# Guitar_Tuner.net
KiCad netlist of a schematic drawn in EAGLE
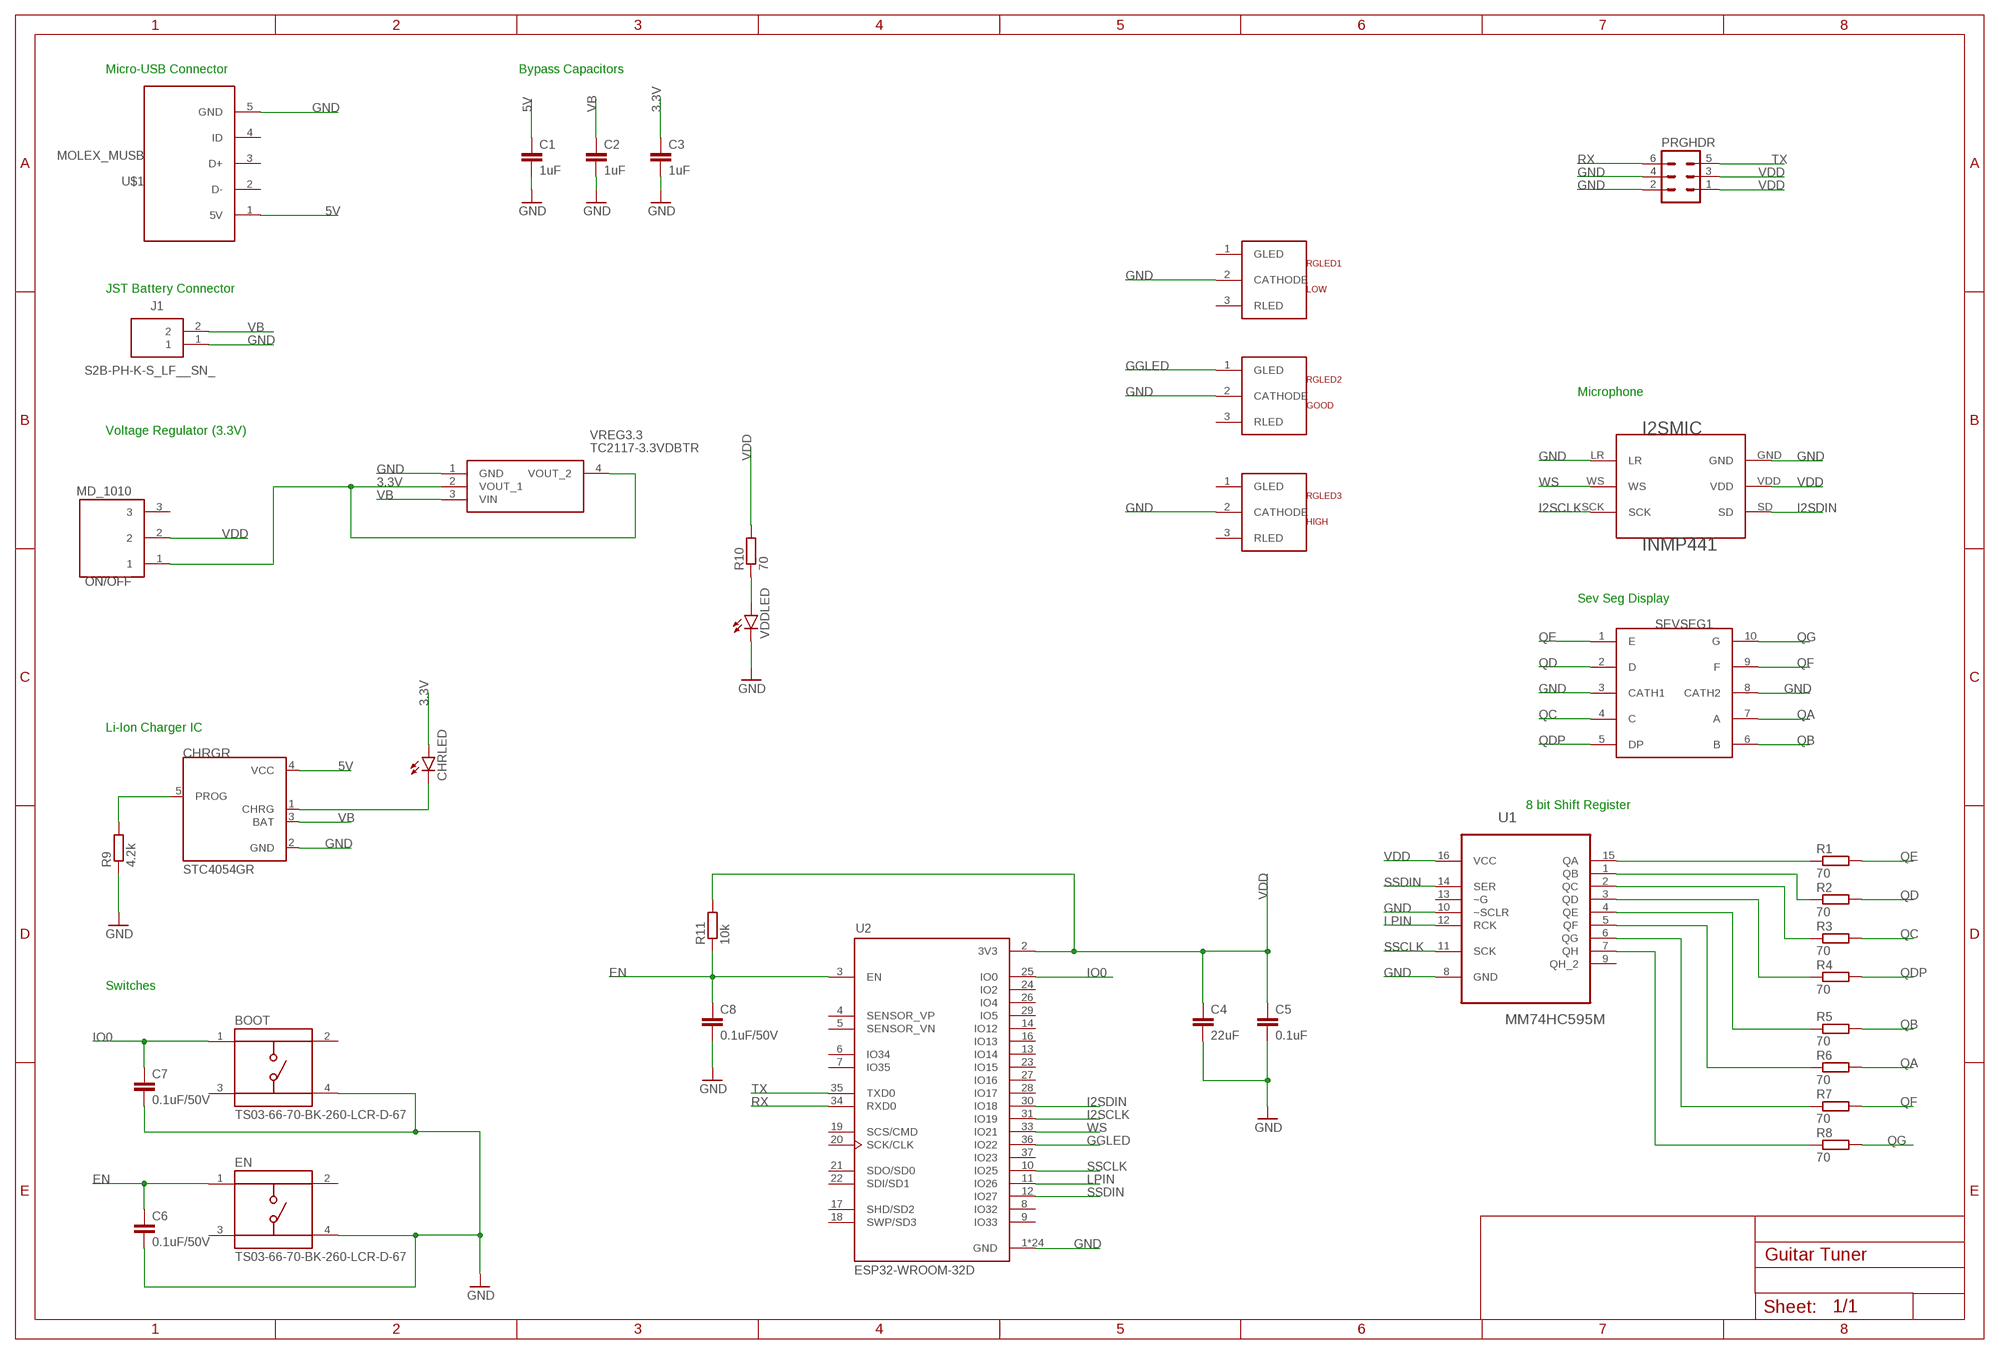
[diagram p0: schematic, sheet 1]

(export (version "E")
  (design (tool "Eeschema 10.0.6"))
  (components
    (comp (ref "BOOT")
      (value "TS03-66-70-BK-260-LCR-D-67")
      (footprint "eagle-import:SW_TS03-66-70-BK-260-LCR-D-67")
      (fields (field (name "MF") "CUI Devices"))
      (libsource (lib "eagle-import") (part "TS03-66-70-BK-260-LCR-D-67"))
    )
    (comp (ref "C1")
      (value "1uF")
      (footprint "eagle-import:C0805")
      (libsource (lib "eagle-import") (part "C-EUC0805"))
    )
    (comp (ref "C2")
      (value "1uF")
      (footprint "eagle-import:C0805")
      (libsource (lib "eagle-import") (part "C-EUC0805"))
    )
    (comp (ref "C3")
      (value "1uF")
      (footprint "eagle-import:C0805")
      (libsource (lib "eagle-import") (part "C-EUC0805"))
    )
    (comp (ref "C4")
      (value "22uF")
      (footprint "eagle-import:C0805")
      (libsource (lib "eagle-import") (part "C-EUC0805"))
    )
    (comp (ref "C5")
      (value "0.1uF")
      (footprint "eagle-import:C0805")
      (libsource (lib "eagle-import") (part "C-EUC0805"))
    )
    (comp (ref "C6")
      (value "0.1uF/50V")
      (footprint "eagle-import:C0805")
      (libsource (lib "eagle-import") (part "C-EUC0805"))
    )
    (comp (ref "C7")
      (value "0.1uF/50V")
      (footprint "eagle-import:C0805")
      (libsource (lib "eagle-import") (part "C-EUC0805"))
    )
    (comp (ref "C8")
      (value "0.1uF/50V")
      (footprint "eagle-import:C0805")
      (libsource (lib "eagle-import") (part "C-EUC0805"))
    )
    (comp (ref "CHRGR")
      (value "STC4054GR")
      (footprint "eagle-import:SOT95P280X110-5N")
      (fields (field (name "MF") "STMicroelectronics"))
      (libsource (lib "eagle-import") (part "STC4054GR"))
    )
    (comp (ref "CHRLED")
      (value "LED5MM")
      (footprint "eagle-import:LED5MM")
      (libsource (lib "eagle-import") (part "LED5MM"))
    )
    (comp (ref "EN")
      (value "TS03-66-70-BK-260-LCR-D-67")
      (footprint "eagle-import:SW_TS03-66-70-BK-260-LCR-D-67")
      (fields (field (name "MF") "CUI Devices"))
      (libsource (lib "eagle-import") (part "TS03-66-70-BK-260-LCR-D-67"))
    )
    (comp (ref "I2SMIC")
      (value "INMP441")
      (footprint "eagle-import:INMP441")
      (libsource (lib "eagle-import") (part "INMP441"))
    )
    (comp (ref "J1")
      (value "S2B-PH-K-S_LF__SN_")
      (footprint "eagle-import:SHDRRA2W50P0X200_1X2_590X760X4")
      (fields (field (name "ARROW_PART_NUMBER") "S2B-PH-K-S(LF)(SN)"))
      (libsource (lib "eagle-import") (part "S2B-PH-K-S_LF__SN_"))
    )
    (comp (ref "ON/OFF")
      (value "MD_1010")
      (footprint "eagle-import:MP_1010")
      (libsource (lib "eagle-import") (part "MD_1010"))
    )
    (comp (ref "PRGHDR")
      (value "MA03-2")
      (footprint "eagle-import:MA03-2")
      (libsource (lib "eagle-import") (part "MA03-2"))
    )
    (comp (ref "R1")
      (value "70")
      (footprint "eagle-import:R0805")
      (libsource (lib "eagle-import") (part "R-EU_R0805"))
    )
    (comp (ref "R2")
      (value "70")
      (footprint "eagle-import:R0805")
      (libsource (lib "eagle-import") (part "R-EU_R0805"))
    )
    (comp (ref "R3")
      (value "70")
      (footprint "eagle-import:R0805")
      (libsource (lib "eagle-import") (part "R-EU_R0805"))
    )
    (comp (ref "R4")
      (value "70")
      (footprint "eagle-import:R0805")
      (libsource (lib "eagle-import") (part "R-EU_R0805"))
    )
    (comp (ref "R5")
      (value "70")
      (footprint "eagle-import:R0805")
      (libsource (lib "eagle-import") (part "R-EU_R0805"))
    )
    (comp (ref "R6")
      (value "70")
      (footprint "eagle-import:R0805")
      (libsource (lib "eagle-import") (part "R-EU_R0805"))
    )
    (comp (ref "R7")
      (value "70")
      (footprint "eagle-import:R0805")
      (libsource (lib "eagle-import") (part "R-EU_R0805"))
    )
    (comp (ref "R8")
      (value "70")
      (footprint "eagle-import:R0805")
      (libsource (lib "eagle-import") (part "R-EU_R0805"))
    )
    (comp (ref "R9")
      (value "4.2k")
      (footprint "eagle-import:R0805")
      (libsource (lib "eagle-import") (part "R-EU_R0805"))
    )
    (comp (ref "R10")
      (value "70")
      (footprint "eagle-import:R0805")
      (libsource (lib "eagle-import") (part "R-EU_R0805"))
    )
    (comp (ref "R11")
      (value "10k")
      (footprint "eagle-import:0207_10")
      (libsource (lib "eagle-import") (part "R-EU_0207/10"))
    )
    (comp (ref "RGLED1")
      (value "LOW")
      (footprint "eagle-import:HLMP-0800")
      (libsource (lib "eagle-import") (part "HLMP-0800"))
    )
    (comp (ref "RGLED2")
      (value "GOOD")
      (footprint "eagle-import:HLMP-0800")
      (libsource (lib "eagle-import") (part "HLMP-0800"))
    )
    (comp (ref "RGLED3")
      (value "HIGH")
      (footprint "eagle-import:HLMP-0800")
      (libsource (lib "eagle-import") (part "HLMP-0800"))
    )
    (comp (ref "SEVSEG1")
      (value "LS0803GWK")
      (footprint "eagle-import:LS0803GWK")
      (libsource (lib "eagle-import") (part "LS0803GWK"))
    )
    (comp (ref "U$1")
      (value "MOLEX_MUSB")
      (footprint "eagle-import:MOLEX_MUSB")
      (libsource (lib "eagle-import") (part "MOLEX_MUSB"))
    )
    (comp (ref "U1")
      (value "MM74HC595M")
      (footprint "eagle-import:SOIC127P600X175-16N")
      (libsource (lib "eagle-import") (part "MM74HC595M"))
    )
    (comp (ref "U2")
      (value "ESP32-WROOM-32D")
      (footprint "eagle-import:MODULE_ESP32-WROOM-32D")
      (fields (field (name "MF") "Espressif Systems"))
      (libsource (lib "eagle-import") (part "ESP32-WROOM-32D"))
    )
    (comp (ref "VDDLED")
      (value "LED5MM")
      (footprint "eagle-import:LED5MM")
      (libsource (lib "eagle-import") (part "LED5MM"))
    )
    (comp (ref "VREG3.3")
      (value "TC2117-3.3VDBTR")
      (footprint "eagle-import:SOT230P700X180-4N")
      (fields (field (name "MOUSER_PART_NUMBER") "579-TC2117-3.3VDBTR"))
      (libsource (lib "eagle-import") (part "TC2117-3.3VDBTR"))
    )
  )
  (nets
    (net (code "1") (name "/3.3V") (class "Default")
      (node (ref "C3") (pin "1") (pinfunction "1_1") (pintype "passive"))
      (node (ref "CHRLED") (pin "A") (pinfunction "A_A") (pintype "passive"))
      (node (ref "ON/OFF") (pin "1") (pinfunction "1_1") (pintype "bidirectional"))
      (node (ref "VREG3.3") (pin "2") (pinfunction "VOUT_1_2") (pintype "power_in"))
      (node (ref "VREG3.3") (pin "4") (pinfunction "VOUT_2_4") (pintype "power_in"))
    )
    (net (code "2") (name "/5V") (class "Default")
      (node (ref "C1") (pin "1") (pinfunction "1_1") (pintype "passive"))
      (node (ref "CHRGR") (pin "4") (pinfunction "VCC_4") (pintype "power_in"))
      (node (ref "U$1") (pin "1") (pinfunction "5V_1") (pintype "bidirectional"))
    )
    (net (code "3") (name "/EN") (class "Default")
      (node (ref "C6") (pin "1") (pinfunction "1_1") (pintype "passive"))
      (node (ref "C8") (pin "1") (pinfunction "1_1") (pintype "passive"))
      (node (ref "EN") (pin "1") (pinfunction "1_1") (pintype "passive"))
      (node (ref "R11") (pin "1") (pinfunction "1_1") (pintype "passive"))
      (node (ref "U2") (pin "3") (pinfunction "EN_3") (pintype "input"))
    )
    (net (code "4") (name "/GGLED") (class "Default")
      (node (ref "RGLED2") (pin "1") (pinfunction "GLED_1") (pintype "bidirectional"))
      (node (ref "U2") (pin "36") (pinfunction "IO22_36") (pintype "bidirectional"))
    )
    (net (code "5") (name "/I2SCLK") (class "Default")
      (node (ref "I2SMIC") (pin "SCK") (pinfunction "SCK_SCK") (pintype "bidirectional"))
      (node (ref "U2") (pin "31") (pinfunction "IO19_31") (pintype "bidirectional"))
    )
    (net (code "6") (name "/I2SDIN") (class "Default")
      (node (ref "I2SMIC") (pin "SD") (pinfunction "SD_SD") (pintype "bidirectional"))
      (node (ref "U2") (pin "30") (pinfunction "IO18_30") (pintype "bidirectional"))
    )
    (net (code "7") (name "/IO0") (class "Default")
      (node (ref "BOOT") (pin "1") (pinfunction "1_1") (pintype "passive"))
      (node (ref "C7") (pin "1") (pinfunction "1_1") (pintype "passive"))
      (node (ref "U2") (pin "25") (pinfunction "IO0_25") (pintype "bidirectional"))
    )
    (net (code "8") (name "/LPIN") (class "Default")
      (node (ref "U1") (pin "12") (pinfunction "RCK_12") (pintype "input"))
      (node (ref "U2") (pin "11") (pinfunction "IO26_11") (pintype "bidirectional"))
    )
    (net (code "9") (name "/QA") (class "Default")
      (node (ref "R6") (pin "2") (pinfunction "2_2") (pintype "passive"))
      (node (ref "SEVSEG1") (pin "7") (pinfunction "A_7") (pintype "bidirectional"))
    )
    (net (code "10") (name "/QB") (class "Default")
      (node (ref "R5") (pin "2") (pinfunction "2_2") (pintype "passive"))
      (node (ref "SEVSEG1") (pin "6") (pinfunction "B_6") (pintype "bidirectional"))
    )
    (net (code "11") (name "/QC") (class "Default")
      (node (ref "R3") (pin "2") (pinfunction "2_2") (pintype "passive"))
      (node (ref "SEVSEG1") (pin "4") (pinfunction "C_4") (pintype "bidirectional"))
    )
    (net (code "12") (name "/QD") (class "Default")
      (node (ref "R2") (pin "2") (pinfunction "2_2") (pintype "passive"))
      (node (ref "SEVSEG1") (pin "2") (pinfunction "D_2") (pintype "bidirectional"))
    )
    (net (code "13") (name "/QDP") (class "Default")
      (node (ref "R4") (pin "2") (pinfunction "2_2") (pintype "passive"))
      (node (ref "SEVSEG1") (pin "5") (pinfunction "DP_5") (pintype "bidirectional"))
    )
    (net (code "14") (name "/QE") (class "Default")
      (node (ref "R1") (pin "2") (pinfunction "2_2") (pintype "passive"))
      (node (ref "SEVSEG1") (pin "1") (pinfunction "E_1") (pintype "bidirectional"))
    )
    (net (code "15") (name "/QF") (class "Default")
      (node (ref "R7") (pin "2") (pinfunction "2_2") (pintype "passive"))
      (node (ref "SEVSEG1") (pin "9") (pinfunction "F_9") (pintype "bidirectional"))
    )
    (net (code "16") (name "/QG") (class "Default")
      (node (ref "R8") (pin "2") (pinfunction "2_2") (pintype "passive"))
      (node (ref "SEVSEG1") (pin "10") (pinfunction "G_10") (pintype "bidirectional"))
    )
    (net (code "17") (name "/RX") (class "Default")
      (node (ref "PRGHDR") (pin "6") (pinfunction "6_6") (pintype "passive"))
      (node (ref "U2") (pin "34") (pinfunction "RXD0_34") (pintype "bidirectional"))
    )
    (net (code "18") (name "/SSCLK") (class "Default")
      (node (ref "U1") (pin "11") (pinfunction "SCK_11") (pintype "input"))
      (node (ref "U2") (pin "10") (pinfunction "IO25_10") (pintype "bidirectional"))
    )
    (net (code "19") (name "/SSDIN") (class "Default")
      (node (ref "U1") (pin "14") (pinfunction "SER_14") (pintype "input"))
      (node (ref "U2") (pin "12") (pinfunction "IO27_12") (pintype "bidirectional"))
    )
    (net (code "20") (name "/TX") (class "Default")
      (node (ref "PRGHDR") (pin "5") (pinfunction "5_5") (pintype "passive"))
      (node (ref "U2") (pin "35") (pinfunction "TXD0_35") (pintype "bidirectional"))
    )
    (net (code "21") (name "/VB") (class "Default")
      (node (ref "C2") (pin "1") (pinfunction "1_1") (pintype "passive"))
      (node (ref "CHRGR") (pin "3") (pinfunction "BAT_3") (pintype "output"))
      (node (ref "J1") (pin "2") (pinfunction "2_2") (pintype "bidirectional"))
      (node (ref "VREG3.3") (pin "3") (pinfunction "VIN_3") (pintype "power_in"))
    )
    (net (code "22") (name "/VDD") (class "Default")
      (node (ref "C4") (pin "1") (pinfunction "1_1") (pintype "passive"))
      (node (ref "C5") (pin "1") (pinfunction "1_1") (pintype "passive"))
      (node (ref "I2SMIC") (pin "VDD") (pinfunction "VDD_VDD") (pintype "bidirectional"))
      (node (ref "ON/OFF") (pin "2") (pinfunction "2_2") (pintype "bidirectional"))
      (node (ref "PRGHDR") (pin "1") (pinfunction "1_1") (pintype "passive"))
      (node (ref "PRGHDR") (pin "3") (pinfunction "3_3") (pintype "passive"))
      (node (ref "R10") (pin "2") (pinfunction "2_2") (pintype "passive"))
      (node (ref "R11") (pin "2") (pinfunction "2_2") (pintype "passive"))
      (node (ref "U1") (pin "16") (pinfunction "VCC_16") (pintype "power_in"))
      (node (ref "U2") (pin "2") (pinfunction "3V3_2") (pintype "power_in"))
    )
    (net (code "23") (name "/WS") (class "Default")
      (node (ref "I2SMIC") (pin "WS") (pinfunction "WS_WS") (pintype "bidirectional"))
      (node (ref "U2") (pin "33") (pinfunction "IO21_33") (pintype "bidirectional"))
    )
    (net (code "24") (name "GND") (class "Default")
      (node (ref "BOOT") (pin "4") (pinfunction "4_4") (pintype "passive"))
      (node (ref "C1") (pin "2") (pinfunction "2_2") (pintype "passive"))
      (node (ref "C2") (pin "2") (pinfunction "2_2") (pintype "passive"))
      (node (ref "C3") (pin "2") (pinfunction "2_2") (pintype "passive"))
      (node (ref "C4") (pin "2") (pinfunction "2_2") (pintype "passive"))
      (node (ref "C5") (pin "2") (pinfunction "2_2") (pintype "passive"))
      (node (ref "C6") (pin "2") (pinfunction "2_2") (pintype "passive"))
      (node (ref "C7") (pin "2") (pinfunction "2_2") (pintype "passive"))
      (node (ref "C8") (pin "2") (pinfunction "2_2") (pintype "passive"))
      (node (ref "CHRGR") (pin "2") (pinfunction "GND_2") (pintype "power_in"))
      (node (ref "EN") (pin "4") (pinfunction "4_4") (pintype "passive"))
      (node (ref "I2SMIC") (pin "GND") (pinfunction "GND_GND") (pintype "bidirectional"))
      (node (ref "I2SMIC") (pin "LR") (pinfunction "LR_LR") (pintype "bidirectional"))
      (node (ref "J1") (pin "1") (pinfunction "1_1") (pintype "bidirectional"))
      (node (ref "PRGHDR") (pin "2") (pinfunction "2_2") (pintype "passive"))
      (node (ref "PRGHDR") (pin "4") (pinfunction "4_4") (pintype "passive"))
      (node (ref "R9") (pin "1") (pinfunction "1_1") (pintype "passive"))
      (node (ref "RGLED1") (pin "2") (pinfunction "CATHODE_2") (pintype "bidirectional"))
      (node (ref "RGLED2") (pin "2") (pinfunction "CATHODE_2") (pintype "bidirectional"))
      (node (ref "RGLED3") (pin "2") (pinfunction "CATHODE_2") (pintype "bidirectional"))
      (node (ref "SEVSEG1") (pin "3") (pinfunction "CATH1_3") (pintype "bidirectional"))
      (node (ref "SEVSEG1") (pin "8") (pinfunction "CATH2_8") (pintype "bidirectional"))
      (node (ref "U$1") (pin "5") (pinfunction "GND_5") (pintype "bidirectional"))
      (node (ref "U1") (pin "10") (pinfunction "~{SCLR}_10") (pintype "input"))
      (node (ref "U1") (pin "8") (pinfunction "GND_8") (pintype "passive"))
      (node (ref "U2") (pin "1") (pinfunction "GND_1") (pintype "power_in"))
      (node (ref "U2") (pin "15") (pinfunction "GND_15") (pintype "power_in"))
      (node (ref "U2") (pin "38") (pinfunction "GND_38") (pintype "power_in"))
      (node (ref "U2") (pin "39_1") (pinfunction "GND_39_1") (pintype "power_in"))
      (node (ref "U2") (pin "39_10") (pinfunction "GND_39_10") (pintype "power_in"))
      (node (ref "U2") (pin "39_11") (pinfunction "GND_39_11") (pintype "power_in"))
      (node (ref "U2") (pin "39_12") (pinfunction "GND_39_12") (pintype "power_in"))
      (node (ref "U2") (pin "39_13") (pinfunction "GND_39_13") (pintype "power_in"))
      (node (ref "U2") (pin "39_14") (pinfunction "GND_39_14") (pintype "power_in"))
      (node (ref "U2") (pin "39_15") (pinfunction "GND_39_15") (pintype "power_in"))
      (node (ref "U2") (pin "39_16") (pinfunction "GND_39_16") (pintype "power_in"))
      (node (ref "U2") (pin "39_17") (pinfunction "GND_39_17") (pintype "power_in"))
      (node (ref "U2") (pin "39_18") (pinfunction "GND_39_18") (pintype "power_in"))
      (node (ref "U2") (pin "39_19") (pinfunction "GND_39_19") (pintype "power_in"))
      (node (ref "U2") (pin "39_2") (pinfunction "GND_39_2") (pintype "power_in"))
      (node (ref "U2") (pin "39_20") (pinfunction "GND_39_20") (pintype "power_in"))
      (node (ref "U2") (pin "39_21") (pinfunction "GND_39_21") (pintype "power_in"))
      (node (ref "U2") (pin "39_3") (pinfunction "GND_39_3") (pintype "power_in"))
      (node (ref "U2") (pin "39_4") (pinfunction "GND_39_4") (pintype "power_in"))
      (node (ref "U2") (pin "39_5") (pinfunction "GND_39_5") (pintype "power_in"))
      (node (ref "U2") (pin "39_6") (pinfunction "GND_39_6") (pintype "power_in"))
      (node (ref "U2") (pin "39_7") (pinfunction "GND_39_7") (pintype "power_in"))
      (node (ref "U2") (pin "39_8") (pinfunction "GND_39_8") (pintype "power_in"))
      (node (ref "U2") (pin "39_9") (pinfunction "GND_39_9") (pintype "power_in"))
      (node (ref "VDDLED") (pin "K") (pinfunction "C_K") (pintype "passive"))
      (node (ref "VREG3.3") (pin "1") (pinfunction "GND_1") (pintype "power_in"))
    )
    (net (code "25") (name "Net-(CHRGR-CHRG)") (class "Default")
      (node (ref "CHRGR") (pin "1") (pinfunction "CHRG_1") (pintype "output"))
      (node (ref "CHRLED") (pin "K") (pinfunction "C_K") (pintype "passive"))
    )
    (net (code "26") (name "Net-(CHRGR-PROG)") (class "Default")
      (node (ref "CHRGR") (pin "5") (pinfunction "PROG_5") (pintype "input"))
      (node (ref "R9") (pin "2") (pinfunction "2_2") (pintype "passive"))
    )
    (net (code "27") (name "Net-(R10-Pad1)") (class "Default")
      (node (ref "R10") (pin "1") (pinfunction "1_1") (pintype "passive"))
      (node (ref "VDDLED") (pin "A") (pinfunction "A_A") (pintype "passive"))
    )
    (net (code "28") (name "Net-(U1-QA)") (class "Default")
      (node (ref "R1") (pin "1") (pinfunction "1_1") (pintype "passive"))
      (node (ref "U1") (pin "15") (pinfunction "QA_15") (pintype "output"))
    )
    (net (code "29") (name "Net-(U1-QB)") (class "Default")
      (node (ref "R2") (pin "1") (pinfunction "1_1") (pintype "passive"))
      (node (ref "U1") (pin "1") (pinfunction "QB_1") (pintype "output"))
    )
    (net (code "30") (name "Net-(U1-QC)") (class "Default")
      (node (ref "R3") (pin "1") (pinfunction "1_1") (pintype "passive"))
      (node (ref "U1") (pin "2") (pinfunction "QC_2") (pintype "output"))
    )
    (net (code "31") (name "Net-(U1-QD)") (class "Default")
      (node (ref "R4") (pin "1") (pinfunction "1_1") (pintype "passive"))
      (node (ref "U1") (pin "3") (pinfunction "QD_3") (pintype "output"))
    )
    (net (code "32") (name "Net-(U1-QE)") (class "Default")
      (node (ref "R5") (pin "1") (pinfunction "1_1") (pintype "passive"))
      (node (ref "U1") (pin "4") (pinfunction "QE_4") (pintype "output"))
    )
    (net (code "33") (name "Net-(U1-QF)") (class "Default")
      (node (ref "R6") (pin "1") (pinfunction "1_1") (pintype "passive"))
      (node (ref "U1") (pin "5") (pinfunction "QF_5") (pintype "output"))
    )
    (net (code "34") (name "Net-(U1-QG)") (class "Default")
      (node (ref "R7") (pin "1") (pinfunction "1_1") (pintype "passive"))
      (node (ref "U1") (pin "6") (pinfunction "QG_6") (pintype "output"))
    )
    (net (code "35") (name "Net-(U1-QH)") (class "Default")
      (node (ref "R8") (pin "1") (pinfunction "1_1") (pintype "passive"))
      (node (ref "U1") (pin "7") (pinfunction "QH_7") (pintype "output"))
    )
    (net (code "36") (name "unconnected-(BOOT-Pad2)") (class "Default")
      (node (ref "BOOT") (pin "2") (pinfunction "2_2") (pintype "passive"))
    )
    (net (code "37") (name "unconnected-(BOOT-Pad3)") (class "Default")
      (node (ref "BOOT") (pin "3") (pinfunction "3_3") (pintype "passive"))
    )
    (net (code "38") (name "unconnected-(EN-Pad2)") (class "Default")
      (node (ref "EN") (pin "2") (pinfunction "2_2") (pintype "passive"))
    )
    (net (code "39") (name "unconnected-(EN-Pad3)") (class "Default")
      (node (ref "EN") (pin "3") (pinfunction "3_3") (pintype "passive"))
    )
    (net (code "40") (name "unconnected-(ON/OFF-Pad3)") (class "Default")
      (node (ref "ON/OFF") (pin "3") (pinfunction "3_3") (pintype "bidirectional"))
    )
    (net (code "41") (name "unconnected-(RGLED1-GLED-Pad1)") (class "Default")
      (node (ref "RGLED1") (pin "1") (pinfunction "GLED_1") (pintype "bidirectional"))
    )
    (net (code "42") (name "unconnected-(RGLED1-RLED-Pad3)") (class "Default")
      (node (ref "RGLED1") (pin "3") (pinfunction "RLED_3") (pintype "bidirectional"))
    )
    (net (code "43") (name "unconnected-(RGLED2-RLED-Pad3)") (class "Default")
      (node (ref "RGLED2") (pin "3") (pinfunction "RLED_3") (pintype "bidirectional"))
    )
    (net (code "44") (name "unconnected-(RGLED3-GLED-Pad1)") (class "Default")
      (node (ref "RGLED3") (pin "1") (pinfunction "GLED_1") (pintype "bidirectional"))
    )
    (net (code "45") (name "unconnected-(RGLED3-RLED-Pad3)") (class "Default")
      (node (ref "RGLED3") (pin "3") (pinfunction "RLED_3") (pintype "bidirectional"))
    )
    (net (code "46") (name "unconnected-(U$1-D+-Pad3)") (class "Default")
      (node (ref "U$1") (pin "3") (pinfunction "D+_3") (pintype "bidirectional"))
    )
    (net (code "47") (name "unconnected-(U$1-D--Pad2)") (class "Default")
      (node (ref "U$1") (pin "2") (pinfunction "D-_2") (pintype "bidirectional"))
    )
    (net (code "48") (name "unconnected-(U$1-ID-Pad4)") (class "Default")
      (node (ref "U$1") (pin "4") (pinfunction "ID_4") (pintype "bidirectional"))
    )
    (net (code "49") (name "unconnected-(U1-QH_2-Pad9)") (class "Default")
      (node (ref "U1") (pin "9") (pinfunction "QH_2_9") (pintype "output"))
    )
    (net (code "50") (name "unconnected-(U1-~{G}-Pad13)") (class "Default")
      (node (ref "U1") (pin "13") (pinfunction "~{G}_13") (pintype "input"))
    )
    (net (code "51") (name "unconnected-(U2-IO2-Pad24)") (class "Default")
      (node (ref "U2") (pin "24") (pinfunction "IO2_24") (pintype "bidirectional"))
    )
    (net (code "52") (name "unconnected-(U2-IO4-Pad26)") (class "Default")
      (node (ref "U2") (pin "26") (pinfunction "IO4_26") (pintype "bidirectional"))
    )
    (net (code "53") (name "unconnected-(U2-IO5-Pad29)") (class "Default")
      (node (ref "U2") (pin "29") (pinfunction "IO5_29") (pintype "bidirectional"))
    )
    (net (code "54") (name "unconnected-(U2-IO12-Pad14)") (class "Default")
      (node (ref "U2") (pin "14") (pinfunction "IO12_14") (pintype "bidirectional"))
    )
    (net (code "55") (name "unconnected-(U2-IO13-Pad16)") (class "Default")
      (node (ref "U2") (pin "16") (pinfunction "IO13_16") (pintype "bidirectional"))
    )
    (net (code "56") (name "unconnected-(U2-IO14-Pad13)") (class "Default")
      (node (ref "U2") (pin "13") (pinfunction "IO14_13") (pintype "bidirectional"))
    )
    (net (code "57") (name "unconnected-(U2-IO15-Pad23)") (class "Default")
      (node (ref "U2") (pin "23") (pinfunction "IO15_23") (pintype "bidirectional"))
    )
    (net (code "58") (name "unconnected-(U2-IO16-Pad27)") (class "Default")
      (node (ref "U2") (pin "27") (pinfunction "IO16_27") (pintype "bidirectional"))
    )
    (net (code "59") (name "unconnected-(U2-IO17-Pad28)") (class "Default")
      (node (ref "U2") (pin "28") (pinfunction "IO17_28") (pintype "bidirectional"))
    )
    (net (code "60") (name "unconnected-(U2-IO23-Pad37)") (class "Default")
      (node (ref "U2") (pin "37") (pinfunction "IO23_37") (pintype "bidirectional"))
    )
    (net (code "61") (name "unconnected-(U2-IO32-Pad8)") (class "Default")
      (node (ref "U2") (pin "8") (pinfunction "IO32_8") (pintype "bidirectional"))
    )
    (net (code "62") (name "unconnected-(U2-IO33-Pad9)") (class "Default")
      (node (ref "U2") (pin "9") (pinfunction "IO33_9") (pintype "bidirectional"))
    )
    (net (code "63") (name "unconnected-(U2-IO34-Pad6)") (class "Default")
      (node (ref "U2") (pin "6") (pinfunction "IO34_6") (pintype "input"))
    )
    (net (code "64") (name "unconnected-(U2-IO35-Pad7)") (class "Default")
      (node (ref "U2") (pin "7") (pinfunction "IO35_7") (pintype "input"))
    )
    (net (code "65") (name "unconnected-(U2-SCK{slash}CLK-Pad20)") (class "Default")
      (node (ref "U2") (pin "20") (pinfunction "SCK/CLK_20") (pintype "bidirectional"))
    )
    (net (code "66") (name "unconnected-(U2-SCS{slash}CMD-Pad19)") (class "Default")
      (node (ref "U2") (pin "19") (pinfunction "SCS/CMD_19") (pintype "bidirectional"))
    )
    (net (code "67") (name "unconnected-(U2-SDI{slash}SD1-Pad22)") (class "Default")
      (node (ref "U2") (pin "22") (pinfunction "SDI/SD1_22") (pintype "bidirectional"))
    )
    (net (code "68") (name "unconnected-(U2-SDO{slash}SD0-Pad21)") (class "Default")
      (node (ref "U2") (pin "21") (pinfunction "SDO/SD0_21") (pintype "bidirectional"))
    )
    (net (code "69") (name "unconnected-(U2-SENSOR_VN-Pad5)") (class "Default")
      (node (ref "U2") (pin "5") (pinfunction "SENSOR_VN_5") (pintype "input"))
    )
    (net (code "70") (name "unconnected-(U2-SENSOR_VP-Pad4)") (class "Default")
      (node (ref "U2") (pin "4") (pinfunction "SENSOR_VP_4") (pintype "input"))
    )
    (net (code "71") (name "unconnected-(U2-SHD{slash}SD2-Pad17)") (class "Default")
      (node (ref "U2") (pin "17") (pinfunction "SHD/SD2_17") (pintype "bidirectional"))
    )
    (net (code "72") (name "unconnected-(U2-SWP{slash}SD3-Pad18)") (class "Default")
      (node (ref "U2") (pin "18") (pinfunction "SWP/SD3_18") (pintype "bidirectional"))
    )
  )
)
